# 1_-PWR_12VIN.net
KiCad netlist of a schematic drawn in Altium Designer
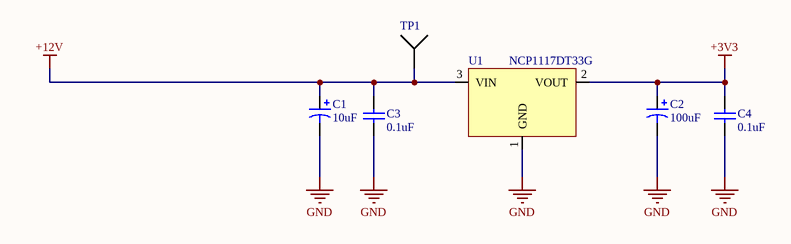
[diagram p0: [1]-PWR_12VIN.SchDoc]

(export (version "E")
  (design (tool "Eeschema 10.0.6"))
  (components
    (comp (ref "C1")
      (value "10uF")
      (footprint "CAP_EEE_C-L")
      (description "CAP ALUM 10UF 20% 25V SMD")
      (fields (field (name "TOLERANCE") "20%") (field (name "VOLTAGE") "25V"))
      (libsource (lib "bitsnio") (part "EEE-1EA100SR"))
    )
    (comp (ref "C2")
      (value "100uF")
      (footprint "CAPAE6553X55M")
      (description "CAP ALUM 100UF 20% 10V SMD")
      (fields (field (name "TOLERANCE") "20%"))
      (libsource (lib "bitsnio") (part "EEE-1AA101WR"))
    )
    (comp (ref "C3")
      (value "0.1uF")
      (footprint "CAPC1608N")
      (description "CAP CER 0.1UF 25V X7R 0603")
      (fields (field (name "TOLERANCE") "10%") (field (name "VOLTAGE") "25V"))
      (libsource (lib "bitsnio") (part "CC0603KRX7R8BB104"))
    )
    (comp (ref "C4")
      (value "0.1uF")
      (footprint "CAPC1608N")
      (description "CAP CER 0.1UF 25V X7R 0603")
      (fields (field (name "TOLERANCE") "10%") (field (name "VOLTAGE") "25V"))
      (libsource (lib "bitsnio") (part "CC0603KRX7R8BB104"))
    )
    (comp (ref "TP1") (value "TP_1_MM") (footprint "TP_1_MM") (libsource (lib "bitsnio") (part "TP_1_MM")))
    (comp (ref "U1")
      (value "NCP1117DT33G")
      (footprint "DPAK-L")
      (description "IC REG LDO 3.3V 1A DPAK")
      (libsource (lib "bitsnio") (part "IC_NCP1117DT33G"))
    )
  )
  (nets
    (net (code "1") (name "+3V3") (class "Default")
      (node (ref "C2") (pin "1") (pinfunction "1_1") (pintype "passive"))
      (node (ref "C4") (pin "2") (pinfunction "2_2") (pintype "passive"))
      (node (ref "U1") (pin "2") (pinfunction "VOUT_2") (pintype "passive"))
    )
    (net (code "2") (name "+12V") (class "Default")
      (node (ref "C1") (pin "2") (pinfunction "2_2") (pintype "passive"))
      (node (ref "C3") (pin "2") (pinfunction "2_2") (pintype "passive"))
      (node (ref "TP1") (pin "1") (pinfunction "1_1") (pintype "passive"))
      (node (ref "U1") (pin "3") (pinfunction "VIN_3") (pintype "passive"))
    )
    (net (code "3") (name "GND") (class "Default")
      (node (ref "C1") (pin "1") (pinfunction "1_1") (pintype "passive"))
      (node (ref "C2") (pin "2") (pinfunction "2_2") (pintype "passive"))
      (node (ref "C3") (pin "1") (pinfunction "1_1") (pintype "passive"))
      (node (ref "C4") (pin "1") (pinfunction "1_1") (pintype "passive"))
      (node (ref "U1") (pin "1") (pinfunction "GND_1") (pintype "passive"))
    )
  )
)
